# luchador.net
KiCad netlist of a schematic drawn in EAGLE
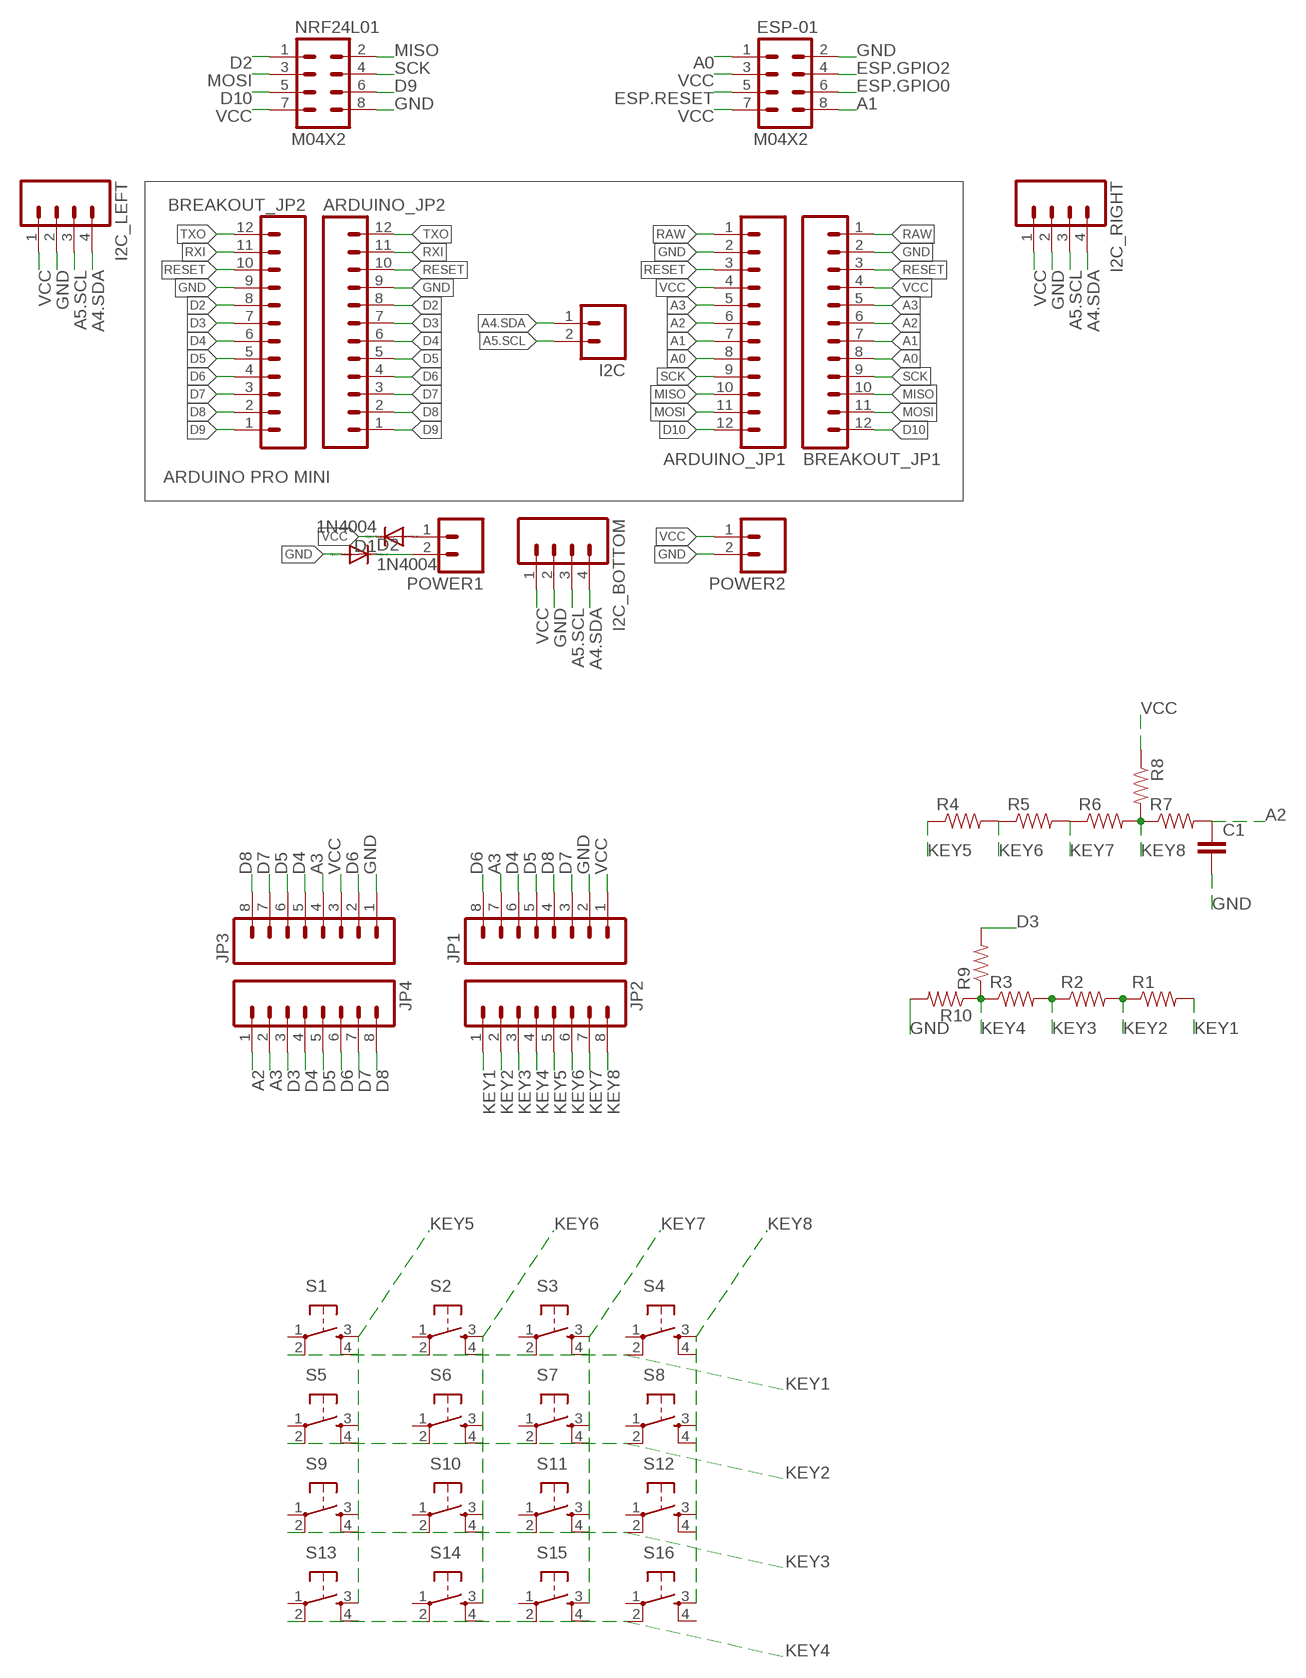
[diagram p0: schematic, sheet 1]

(export (version "E")
  (design (tool "Eeschema 10.0.6"))
  (components
    (comp (ref "ARDUINO_JP1")
      (value "M12PTH")
      (footprint "eagle-import:1X12")
      (libsource (lib "eagle-import") (part "M12PTH"))
    )
    (comp (ref "ARDUINO_JP2")
      (value "M12PTH")
      (footprint "eagle-import:1X12")
      (libsource (lib "eagle-import") (part "M12PTH"))
    )
    (comp (ref "BREAKOUT_JP1")
      (value "M12PTH")
      (footprint "eagle-import:1X12")
      (libsource (lib "eagle-import") (part "M12PTH"))
    )
    (comp (ref "BREAKOUT_JP2")
      (value "M12PTH")
      (footprint "eagle-import:1X12")
      (libsource (lib "eagle-import") (part "M12PTH"))
    )
    (comp (ref "C1")
      (value "CAP_")
      (footprint "eagle-import:AXIAL-5MM")
      (libsource (lib "eagle-import") (part "CAP_"))
    )
    (comp (ref "D1")
      (value "1N4004")
      (footprint "eagle-import:DO41-10")
      (libsource (lib "eagle-import") (part "1N4004"))
    )
    (comp (ref "D2")
      (value "1N4004")
      (footprint "eagle-import:DO41-10")
      (libsource (lib "eagle-import") (part "1N4004"))
    )
    (comp (ref "ESP-01")
      (value "M04X2")
      (footprint "eagle-import:2X4")
      (libsource (lib "eagle-import") (part "M04X2"))
    )
    (comp (ref "I2C")
      (value "M02PTH")
      (footprint "eagle-import:1X02")
      (libsource (lib "eagle-import") (part "M02PTH"))
    )
    (comp (ref "I2C_BOTTOM")
      (value "M04PTH")
      (footprint "eagle-import:1X04")
      (libsource (lib "eagle-import") (part "M04PTH"))
    )
    (comp (ref "I2C_LEFT")
      (value "M04PTH")
      (footprint "eagle-import:1X04")
      (libsource (lib "eagle-import") (part "M04PTH"))
    )
    (comp (ref "I2C_RIGHT")
      (value "M04PTH")
      (footprint "eagle-import:1X04")
      (libsource (lib "eagle-import") (part "M04PTH"))
    )
    (comp (ref "JP1")
      (value "M08SILK_FEMALE_PTH")
      (footprint "eagle-import:1X08")
      (libsource (lib "eagle-import") (part "M08SILK_FEMALE_PTH"))
    )
    (comp (ref "JP2")
      (value "M08SILK_FEMALE_PTH")
      (footprint "eagle-import:1X08")
      (libsource (lib "eagle-import") (part "M08SILK_FEMALE_PTH"))
    )
    (comp (ref "JP3")
      (value "M08SILK_FEMALE_PTH")
      (footprint "eagle-import:1X08")
      (libsource (lib "eagle-import") (part "M08SILK_FEMALE_PTH"))
    )
    (comp (ref "JP4")
      (value "M08SILK_FEMALE_PTH")
      (footprint "eagle-import:1X08")
      (libsource (lib "eagle-import") (part "M08SILK_FEMALE_PTH"))
    )
    (comp (ref "NRF24L01")
      (value "M04X2")
      (footprint "eagle-import:2X4")
      (libsource (lib "eagle-import") (part "M04X2"))
    )
    (comp (ref "POWER1")
      (value "M02PTH")
      (footprint "eagle-import:1X02")
      (libsource (lib "eagle-import") (part "M02PTH"))
    )
    (comp (ref "POWER2")
      (value "M02PTH")
      (footprint "eagle-import:1X02")
      (libsource (lib "eagle-import") (part "M02PTH"))
    )
    (comp (ref "R1")
      (value "RESISTORAXIAL-0.3")
      (footprint "eagle-import:AXIAL-0.3")
      (libsource (lib "eagle-import") (part "RESISTORAXIAL-0.3"))
    )
    (comp (ref "R2")
      (value "RESISTORAXIAL-0.3")
      (footprint "eagle-import:AXIAL-0.3")
      (libsource (lib "eagle-import") (part "RESISTORAXIAL-0.3"))
    )
    (comp (ref "R3")
      (value "RESISTORAXIAL-0.3")
      (footprint "eagle-import:AXIAL-0.3")
      (libsource (lib "eagle-import") (part "RESISTORAXIAL-0.3"))
    )
    (comp (ref "R4")
      (value "RESISTORAXIAL-0.3")
      (footprint "eagle-import:AXIAL-0.3")
      (libsource (lib "eagle-import") (part "RESISTORAXIAL-0.3"))
    )
    (comp (ref "R5")
      (value "RESISTORAXIAL-0.3")
      (footprint "eagle-import:AXIAL-0.3")
      (libsource (lib "eagle-import") (part "RESISTORAXIAL-0.3"))
    )
    (comp (ref "R6")
      (value "RESISTORAXIAL-0.3")
      (footprint "eagle-import:AXIAL-0.3")
      (libsource (lib "eagle-import") (part "RESISTORAXIAL-0.3"))
    )
    (comp (ref "R7")
      (value "RESISTORAXIAL-0.3")
      (footprint "eagle-import:AXIAL-0.3")
      (libsource (lib "eagle-import") (part "RESISTORAXIAL-0.3"))
    )
    (comp (ref "R8")
      (value "RESISTORAXIAL-0.3")
      (footprint "eagle-import:AXIAL-0.3")
      (libsource (lib "eagle-import") (part "RESISTORAXIAL-0.3"))
    )
    (comp (ref "R9")
      (value "RESISTORAXIAL-0.3")
      (footprint "eagle-import:AXIAL-0.3")
      (libsource (lib "eagle-import") (part "RESISTORAXIAL-0.3"))
    )
    (comp (ref "R10")
      (value "RESISTORAXIAL-0.3")
      (footprint "eagle-import:AXIAL-0.3")
      (libsource (lib "eagle-import") (part "RESISTORAXIAL-0.3"))
    )
    (comp (ref "S1")
      (value "TAC_SWITCHPTH")
      (footprint "eagle-import:TACTILE-PTH")
      (libsource (lib "eagle-import") (part "TAC_SWITCHPTH"))
    )
    (comp (ref "S2")
      (value "TAC_SWITCHPTH")
      (footprint "eagle-import:TACTILE-PTH")
      (libsource (lib "eagle-import") (part "TAC_SWITCHPTH"))
    )
    (comp (ref "S3")
      (value "TAC_SWITCHPTH")
      (footprint "eagle-import:TACTILE-PTH")
      (libsource (lib "eagle-import") (part "TAC_SWITCHPTH"))
    )
    (comp (ref "S4")
      (value "TAC_SWITCHPTH")
      (footprint "eagle-import:TACTILE-PTH")
      (libsource (lib "eagle-import") (part "TAC_SWITCHPTH"))
    )
    (comp (ref "S5")
      (value "TAC_SWITCHPTH")
      (footprint "eagle-import:TACTILE-PTH")
      (libsource (lib "eagle-import") (part "TAC_SWITCHPTH"))
    )
    (comp (ref "S6")
      (value "TAC_SWITCHPTH")
      (footprint "eagle-import:TACTILE-PTH")
      (libsource (lib "eagle-import") (part "TAC_SWITCHPTH"))
    )
    (comp (ref "S7")
      (value "TAC_SWITCHPTH")
      (footprint "eagle-import:TACTILE-PTH")
      (libsource (lib "eagle-import") (part "TAC_SWITCHPTH"))
    )
    (comp (ref "S8")
      (value "TAC_SWITCHPTH")
      (footprint "eagle-import:TACTILE-PTH")
      (libsource (lib "eagle-import") (part "TAC_SWITCHPTH"))
    )
    (comp (ref "S9")
      (value "TAC_SWITCHPTH")
      (footprint "eagle-import:TACTILE-PTH")
      (libsource (lib "eagle-import") (part "TAC_SWITCHPTH"))
    )
    (comp (ref "S10")
      (value "TAC_SWITCHPTH")
      (footprint "eagle-import:TACTILE-PTH")
      (libsource (lib "eagle-import") (part "TAC_SWITCHPTH"))
    )
    (comp (ref "S11")
      (value "TAC_SWITCHPTH")
      (footprint "eagle-import:TACTILE-PTH")
      (libsource (lib "eagle-import") (part "TAC_SWITCHPTH"))
    )
    (comp (ref "S12")
      (value "TAC_SWITCHPTH")
      (footprint "eagle-import:TACTILE-PTH")
      (libsource (lib "eagle-import") (part "TAC_SWITCHPTH"))
    )
    (comp (ref "S13")
      (value "TAC_SWITCHPTH")
      (footprint "eagle-import:TACTILE-PTH")
      (libsource (lib "eagle-import") (part "TAC_SWITCHPTH"))
    )
    (comp (ref "S14")
      (value "TAC_SWITCHPTH")
      (footprint "eagle-import:TACTILE-PTH")
      (libsource (lib "eagle-import") (part "TAC_SWITCHPTH"))
    )
    (comp (ref "S15")
      (value "TAC_SWITCHPTH")
      (footprint "eagle-import:TACTILE-PTH")
      (libsource (lib "eagle-import") (part "TAC_SWITCHPTH"))
    )
    (comp (ref "S16")
      (value "TAC_SWITCHPTH")
      (footprint "eagle-import:TACTILE-PTH")
      (libsource (lib "eagle-import") (part "TAC_SWITCHPTH"))
    )
  )
  (nets
    (net (code "1") (name "/ESP.GPIO0") (class "Default")
      (node (ref "ESP-01") (pin "6") (pinfunction "6_6") (pintype "passive"))
    )
    (net (code "2") (name "/ESP.GPIO2") (class "Default")
      (node (ref "ESP-01") (pin "4") (pinfunction "4_4") (pintype "passive"))
    )
    (net (code "3") (name "/ESP.RESET") (class "Default")
      (node (ref "ESP-01") (pin "5") (pinfunction "5_5") (pintype "passive"))
    )
    (net (code "4") (name "/KEY1") (class "Default")
      (node (ref "JP2") (pin "1") (pinfunction "1_1") (pintype "passive"))
      (node (ref "R1") (pin "P$2") (pinfunction "2_P$2") (pintype "passive"))
      (node (ref "S1") (pin "2") (pinfunction "2_2") (pintype "passive"))
      (node (ref "S2") (pin "2") (pinfunction "2_2") (pintype "passive"))
      (node (ref "S3") (pin "2") (pinfunction "2_2") (pintype "passive"))
      (node (ref "S4") (pin "2") (pinfunction "2_2") (pintype "passive"))
    )
    (net (code "5") (name "/KEY2") (class "Default")
      (node (ref "JP2") (pin "2") (pinfunction "2_2") (pintype "passive"))
      (node (ref "R1") (pin "P$1") (pinfunction "1_P$1") (pintype "passive"))
      (node (ref "R2") (pin "P$2") (pinfunction "2_P$2") (pintype "passive"))
      (node (ref "S5") (pin "2") (pinfunction "2_2") (pintype "passive"))
      (node (ref "S6") (pin "2") (pinfunction "2_2") (pintype "passive"))
      (node (ref "S7") (pin "2") (pinfunction "2_2") (pintype "passive"))
      (node (ref "S8") (pin "2") (pinfunction "2_2") (pintype "passive"))
    )
    (net (code "6") (name "/KEY3") (class "Default")
      (node (ref "JP2") (pin "3") (pinfunction "3_3") (pintype "passive"))
      (node (ref "R2") (pin "P$1") (pinfunction "1_P$1") (pintype "passive"))
      (node (ref "R3") (pin "P$2") (pinfunction "2_P$2") (pintype "passive"))
      (node (ref "S10") (pin "2") (pinfunction "2_2") (pintype "passive"))
      (node (ref "S11") (pin "2") (pinfunction "2_2") (pintype "passive"))
      (node (ref "S12") (pin "2") (pinfunction "2_2") (pintype "passive"))
      (node (ref "S9") (pin "2") (pinfunction "2_2") (pintype "passive"))
    )
    (net (code "7") (name "/KEY4") (class "Default")
      (node (ref "JP2") (pin "4") (pinfunction "4_4") (pintype "passive"))
      (node (ref "R10") (pin "P$1") (pinfunction "1_P$1") (pintype "passive"))
      (node (ref "R3") (pin "P$1") (pinfunction "1_P$1") (pintype "passive"))
      (node (ref "R9") (pin "P$1") (pinfunction "1_P$1") (pintype "passive"))
      (node (ref "S13") (pin "2") (pinfunction "2_2") (pintype "passive"))
      (node (ref "S14") (pin "2") (pinfunction "2_2") (pintype "passive"))
      (node (ref "S15") (pin "2") (pinfunction "2_2") (pintype "passive"))
      (node (ref "S16") (pin "2") (pinfunction "2_2") (pintype "passive"))
    )
    (net (code "8") (name "/KEY5") (class "Default")
      (node (ref "JP2") (pin "5") (pinfunction "5_5") (pintype "passive"))
      (node (ref "R4") (pin "P$1") (pinfunction "1_P$1") (pintype "passive"))
      (node (ref "S1") (pin "3") (pinfunction "3_3") (pintype "passive"))
      (node (ref "S13") (pin "3") (pinfunction "3_3") (pintype "passive"))
      (node (ref "S5") (pin "3") (pinfunction "3_3") (pintype "passive"))
      (node (ref "S9") (pin "3") (pinfunction "3_3") (pintype "passive"))
    )
    (net (code "9") (name "/KEY6") (class "Default")
      (node (ref "JP2") (pin "6") (pinfunction "6_6") (pintype "passive"))
      (node (ref "R4") (pin "P$2") (pinfunction "2_P$2") (pintype "passive"))
      (node (ref "R5") (pin "P$1") (pinfunction "1_P$1") (pintype "passive"))
      (node (ref "S10") (pin "3") (pinfunction "3_3") (pintype "passive"))
      (node (ref "S14") (pin "3") (pinfunction "3_3") (pintype "passive"))
      (node (ref "S2") (pin "3") (pinfunction "3_3") (pintype "passive"))
      (node (ref "S6") (pin "3") (pinfunction "3_3") (pintype "passive"))
    )
    (net (code "10") (name "/KEY7") (class "Default")
      (node (ref "JP2") (pin "7") (pinfunction "7_7") (pintype "passive"))
      (node (ref "R5") (pin "P$2") (pinfunction "2_P$2") (pintype "passive"))
      (node (ref "R6") (pin "P$1") (pinfunction "1_P$1") (pintype "passive"))
      (node (ref "S11") (pin "3") (pinfunction "3_3") (pintype "passive"))
      (node (ref "S15") (pin "3") (pinfunction "3_3") (pintype "passive"))
      (node (ref "S3") (pin "3") (pinfunction "3_3") (pintype "passive"))
      (node (ref "S7") (pin "3") (pinfunction "3_3") (pintype "passive"))
    )
    (net (code "11") (name "/KEY8") (class "Default")
      (node (ref "JP2") (pin "8") (pinfunction "8_8") (pintype "passive"))
      (node (ref "R6") (pin "P$2") (pinfunction "2_P$2") (pintype "passive"))
      (node (ref "R7") (pin "P$1") (pinfunction "1_P$1") (pintype "passive"))
      (node (ref "R8") (pin "P$2") (pinfunction "2_P$2") (pintype "passive"))
      (node (ref "S12") (pin "3") (pinfunction "3_3") (pintype "passive"))
      (node (ref "S16") (pin "3") (pinfunction "3_3") (pintype "passive"))
      (node (ref "S4") (pin "3") (pinfunction "3_3") (pintype "passive"))
      (node (ref "S8") (pin "3") (pinfunction "3_3") (pintype "passive"))
    )
    (net (code "12") (name "A0") (class "Default")
      (node (ref "ARDUINO_JP1") (pin "8") (pinfunction "8_8") (pintype "passive"))
      (node (ref "BREAKOUT_JP1") (pin "8") (pinfunction "8_8") (pintype "passive"))
      (node (ref "ESP-01") (pin "1") (pinfunction "1_1") (pintype "passive"))
    )
    (net (code "13") (name "A1") (class "Default")
      (node (ref "ARDUINO_JP1") (pin "7") (pinfunction "7_7") (pintype "passive"))
      (node (ref "BREAKOUT_JP1") (pin "7") (pinfunction "7_7") (pintype "passive"))
      (node (ref "ESP-01") (pin "8") (pinfunction "8_8") (pintype "passive"))
    )
    (net (code "14") (name "A2") (class "Default")
      (node (ref "ARDUINO_JP1") (pin "6") (pinfunction "6_6") (pintype "passive"))
      (node (ref "BREAKOUT_JP1") (pin "6") (pinfunction "6_6") (pintype "passive"))
      (node (ref "C1") (pin "P$1") (pinfunction "1_P$1") (pintype "passive"))
      (node (ref "JP4") (pin "1") (pinfunction "1_1") (pintype "passive"))
      (node (ref "R7") (pin "P$2") (pinfunction "2_P$2") (pintype "passive"))
    )
    (net (code "15") (name "A3") (class "Default")
      (node (ref "ARDUINO_JP1") (pin "5") (pinfunction "5_5") (pintype "passive"))
      (node (ref "BREAKOUT_JP1") (pin "5") (pinfunction "5_5") (pintype "passive"))
      (node (ref "JP1") (pin "7") (pinfunction "7_7") (pintype "passive"))
      (node (ref "JP3") (pin "4") (pinfunction "4_4") (pintype "passive"))
      (node (ref "JP4") (pin "2") (pinfunction "2_2") (pintype "passive"))
    )
    (net (code "16") (name "A4.SDA") (class "Default")
      (node (ref "I2C") (pin "1") (pinfunction "1_1") (pintype "passive"))
      (node (ref "I2C_BOTTOM") (pin "4") (pinfunction "4_4") (pintype "passive"))
      (node (ref "I2C_LEFT") (pin "4") (pinfunction "4_4") (pintype "passive"))
      (node (ref "I2C_RIGHT") (pin "4") (pinfunction "4_4") (pintype "passive"))
    )
    (net (code "17") (name "A5.SCL") (class "Default")
      (node (ref "I2C") (pin "2") (pinfunction "2_2") (pintype "passive"))
      (node (ref "I2C_BOTTOM") (pin "3") (pinfunction "3_3") (pintype "passive"))
      (node (ref "I2C_LEFT") (pin "3") (pinfunction "3_3") (pintype "passive"))
      (node (ref "I2C_RIGHT") (pin "3") (pinfunction "3_3") (pintype "passive"))
    )
    (net (code "18") (name "D2") (class "Default")
      (node (ref "ARDUINO_JP2") (pin "8") (pinfunction "8_8") (pintype "passive"))
      (node (ref "BREAKOUT_JP2") (pin "8") (pinfunction "8_8") (pintype "passive"))
      (node (ref "NRF24L01") (pin "1") (pinfunction "1_1") (pintype "passive"))
    )
    (net (code "19") (name "D3") (class "Default")
      (node (ref "ARDUINO_JP2") (pin "7") (pinfunction "7_7") (pintype "passive"))
      (node (ref "BREAKOUT_JP2") (pin "7") (pinfunction "7_7") (pintype "passive"))
      (node (ref "JP4") (pin "3") (pinfunction "3_3") (pintype "passive"))
      (node (ref "R9") (pin "P$2") (pinfunction "2_P$2") (pintype "passive"))
    )
    (net (code "20") (name "D4") (class "Default")
      (node (ref "ARDUINO_JP2") (pin "6") (pinfunction "6_6") (pintype "passive"))
      (node (ref "BREAKOUT_JP2") (pin "6") (pinfunction "6_6") (pintype "passive"))
      (node (ref "JP1") (pin "6") (pinfunction "6_6") (pintype "passive"))
      (node (ref "JP3") (pin "5") (pinfunction "5_5") (pintype "passive"))
      (node (ref "JP4") (pin "4") (pinfunction "4_4") (pintype "passive"))
    )
    (net (code "21") (name "D5") (class "Default")
      (node (ref "ARDUINO_JP2") (pin "5") (pinfunction "5_5") (pintype "passive"))
      (node (ref "BREAKOUT_JP2") (pin "5") (pinfunction "5_5") (pintype "passive"))
      (node (ref "JP1") (pin "5") (pinfunction "5_5") (pintype "passive"))
      (node (ref "JP3") (pin "6") (pinfunction "6_6") (pintype "passive"))
      (node (ref "JP4") (pin "5") (pinfunction "5_5") (pintype "passive"))
    )
    (net (code "22") (name "D6") (class "Default")
      (node (ref "ARDUINO_JP2") (pin "4") (pinfunction "4_4") (pintype "passive"))
      (node (ref "BREAKOUT_JP2") (pin "4") (pinfunction "4_4") (pintype "passive"))
      (node (ref "JP1") (pin "8") (pinfunction "8_8") (pintype "passive"))
      (node (ref "JP3") (pin "2") (pinfunction "2_2") (pintype "passive"))
      (node (ref "JP4") (pin "6") (pinfunction "6_6") (pintype "passive"))
    )
    (net (code "23") (name "D7") (class "Default")
      (node (ref "ARDUINO_JP2") (pin "3") (pinfunction "3_3") (pintype "passive"))
      (node (ref "BREAKOUT_JP2") (pin "3") (pinfunction "3_3") (pintype "passive"))
      (node (ref "JP1") (pin "3") (pinfunction "3_3") (pintype "passive"))
      (node (ref "JP3") (pin "7") (pinfunction "7_7") (pintype "passive"))
      (node (ref "JP4") (pin "7") (pinfunction "7_7") (pintype "passive"))
    )
    (net (code "24") (name "D8") (class "Default")
      (node (ref "ARDUINO_JP2") (pin "2") (pinfunction "2_2") (pintype "passive"))
      (node (ref "BREAKOUT_JP2") (pin "2") (pinfunction "2_2") (pintype "passive"))
      (node (ref "JP1") (pin "4") (pinfunction "4_4") (pintype "passive"))
      (node (ref "JP3") (pin "8") (pinfunction "8_8") (pintype "passive"))
      (node (ref "JP4") (pin "8") (pinfunction "8_8") (pintype "passive"))
    )
    (net (code "25") (name "D9") (class "Default")
      (node (ref "ARDUINO_JP2") (pin "1") (pinfunction "1_1") (pintype "passive"))
      (node (ref "BREAKOUT_JP2") (pin "1") (pinfunction "1_1") (pintype "passive"))
      (node (ref "NRF24L01") (pin "6") (pinfunction "6_6") (pintype "passive"))
    )
    (net (code "26") (name "D10") (class "Default")
      (node (ref "ARDUINO_JP1") (pin "12") (pinfunction "12_12") (pintype "passive"))
      (node (ref "BREAKOUT_JP1") (pin "12") (pinfunction "12_12") (pintype "passive"))
      (node (ref "NRF24L01") (pin "5") (pinfunction "5_5") (pintype "passive"))
    )
    (net (code "27") (name "GND") (class "Default")
      (node (ref "ARDUINO_JP1") (pin "2") (pinfunction "2_2") (pintype "passive"))
      (node (ref "ARDUINO_JP2") (pin "9") (pinfunction "9_9") (pintype "passive"))
      (node (ref "BREAKOUT_JP1") (pin "2") (pinfunction "2_2") (pintype "passive"))
      (node (ref "BREAKOUT_JP2") (pin "9") (pinfunction "9_9") (pintype "passive"))
      (node (ref "C1") (pin "P$2") (pinfunction "2_P$2") (pintype "passive"))
      (node (ref "D2") (pin "A") (pinfunction "A_A") (pintype "passive"))
      (node (ref "ESP-01") (pin "2") (pinfunction "2_2") (pintype "passive"))
      (node (ref "I2C_BOTTOM") (pin "2") (pinfunction "2_2") (pintype "passive"))
      (node (ref "I2C_LEFT") (pin "2") (pinfunction "2_2") (pintype "passive"))
      (node (ref "I2C_RIGHT") (pin "2") (pinfunction "2_2") (pintype "passive"))
      (node (ref "JP1") (pin "2") (pinfunction "2_2") (pintype "passive"))
      (node (ref "JP3") (pin "1") (pinfunction "1_1") (pintype "passive"))
      (node (ref "NRF24L01") (pin "8") (pinfunction "8_8") (pintype "passive"))
      (node (ref "POWER2") (pin "2") (pinfunction "2_2") (pintype "passive"))
      (node (ref "R10") (pin "P$2") (pinfunction "2_P$2") (pintype "passive"))
    )
    (net (code "28") (name "MISO") (class "Default")
      (node (ref "ARDUINO_JP1") (pin "10") (pinfunction "10_10") (pintype "passive"))
      (node (ref "BREAKOUT_JP1") (pin "10") (pinfunction "10_10") (pintype "passive"))
      (node (ref "NRF24L01") (pin "2") (pinfunction "2_2") (pintype "passive"))
    )
    (net (code "29") (name "MOSI") (class "Default")
      (node (ref "ARDUINO_JP1") (pin "11") (pinfunction "11_11") (pintype "passive"))
      (node (ref "BREAKOUT_JP1") (pin "11") (pinfunction "11_11") (pintype "passive"))
      (node (ref "NRF24L01") (pin "3") (pinfunction "3_3") (pintype "passive"))
    )
    (net (code "30") (name "Net-(D1-PadA)") (class "Default")
      (node (ref "D1") (pin "A") (pinfunction "A_A") (pintype "passive"))
      (node (ref "POWER1") (pin "1") (pinfunction "1_1") (pintype "passive"))
    )
    (net (code "31") (name "Net-(D2-PadC)") (class "Default")
      (node (ref "D2") (pin "C") (pinfunction "C_C") (pintype "passive"))
      (node (ref "POWER1") (pin "2") (pinfunction "2_2") (pintype "passive"))
    )
    (net (code "32") (name "RAW") (class "Default")
      (node (ref "ARDUINO_JP1") (pin "1") (pinfunction "1_1") (pintype "passive"))
      (node (ref "BREAKOUT_JP1") (pin "1") (pinfunction "1_1") (pintype "passive"))
    )
    (net (code "33") (name "RESET") (class "Default")
      (node (ref "ARDUINO_JP1") (pin "3") (pinfunction "3_3") (pintype "passive"))
      (node (ref "ARDUINO_JP2") (pin "10") (pinfunction "10_10") (pintype "passive"))
      (node (ref "BREAKOUT_JP1") (pin "3") (pinfunction "3_3") (pintype "passive"))
      (node (ref "BREAKOUT_JP2") (pin "10") (pinfunction "10_10") (pintype "passive"))
    )
    (net (code "34") (name "RXI") (class "Default")
      (node (ref "ARDUINO_JP2") (pin "11") (pinfunction "11_11") (pintype "passive"))
      (node (ref "BREAKOUT_JP2") (pin "11") (pinfunction "11_11") (pintype "passive"))
    )
    (net (code "35") (name "SCK") (class "Default")
      (node (ref "ARDUINO_JP1") (pin "9") (pinfunction "9_9") (pintype "passive"))
      (node (ref "BREAKOUT_JP1") (pin "9") (pinfunction "9_9") (pintype "passive"))
      (node (ref "NRF24L01") (pin "4") (pinfunction "4_4") (pintype "passive"))
    )
    (net (code "36") (name "TXO") (class "Default")
      (node (ref "ARDUINO_JP2") (pin "12") (pinfunction "12_12") (pintype "passive"))
      (node (ref "BREAKOUT_JP2") (pin "12") (pinfunction "12_12") (pintype "passive"))
    )
    (net (code "37") (name "VCC") (class "Default")
      (node (ref "ARDUINO_JP1") (pin "4") (pinfunction "4_4") (pintype "passive"))
      (node (ref "BREAKOUT_JP1") (pin "4") (pinfunction "4_4") (pintype "passive"))
      (node (ref "D1") (pin "C") (pinfunction "C_C") (pintype "passive"))
      (node (ref "ESP-01") (pin "3") (pinfunction "3_3") (pintype "passive"))
      (node (ref "ESP-01") (pin "7") (pinfunction "7_7") (pintype "passive"))
      (node (ref "I2C_BOTTOM") (pin "1") (pinfunction "1_1") (pintype "passive"))
      (node (ref "I2C_LEFT") (pin "1") (pinfunction "1_1") (pintype "passive"))
      (node (ref "I2C_RIGHT") (pin "1") (pinfunction "1_1") (pintype "passive"))
      (node (ref "JP1") (pin "1") (pinfunction "1_1") (pintype "passive"))
      (node (ref "JP3") (pin "3") (pinfunction "3_3") (pintype "passive"))
      (node (ref "NRF24L01") (pin "7") (pinfunction "7_7") (pintype "passive"))
      (node (ref "POWER2") (pin "1") (pinfunction "1_1") (pintype "passive"))
      (node (ref "R8") (pin "P$1") (pinfunction "1_P$1") (pintype "passive"))
    )
    (net (code "38") (name "unconnected-(S1-Pad1)") (class "Default")
      (node (ref "S1") (pin "1") (pinfunction "1_1") (pintype "passive"))
    )
    (net (code "39") (name "unconnected-(S1-Pad4)") (class "Default")
      (node (ref "S1") (pin "4") (pinfunction "4_4") (pintype "passive"))
    )
    (net (code "40") (name "unconnected-(S2-Pad1)") (class "Default")
      (node (ref "S2") (pin "1") (pinfunction "1_1") (pintype "passive"))
    )
    (net (code "41") (name "unconnected-(S2-Pad4)") (class "Default")
      (node (ref "S2") (pin "4") (pinfunction "4_4") (pintype "passive"))
    )
    (net (code "42") (name "unconnected-(S3-Pad1)") (class "Default")
      (node (ref "S3") (pin "1") (pinfunction "1_1") (pintype "passive"))
    )
    (net (code "43") (name "unconnected-(S3-Pad4)") (class "Default")
      (node (ref "S3") (pin "4") (pinfunction "4_4") (pintype "passive"))
    )
    (net (code "44") (name "unconnected-(S4-Pad1)") (class "Default")
      (node (ref "S4") (pin "1") (pinfunction "1_1") (pintype "passive"))
    )
    (net (code "45") (name "unconnected-(S4-Pad4)") (class "Default")
      (node (ref "S4") (pin "4") (pinfunction "4_4") (pintype "passive"))
    )
    (net (code "46") (name "unconnected-(S5-Pad1)") (class "Default")
      (node (ref "S5") (pin "1") (pinfunction "1_1") (pintype "passive"))
    )
    (net (code "47") (name "unconnected-(S5-Pad4)") (class "Default")
      (node (ref "S5") (pin "4") (pinfunction "4_4") (pintype "passive"))
    )
    (net (code "48") (name "unconnected-(S6-Pad1)") (class "Default")
      (node (ref "S6") (pin "1") (pinfunction "1_1") (pintype "passive"))
    )
    (net (code "49") (name "unconnected-(S6-Pad4)") (class "Default")
      (node (ref "S6") (pin "4") (pinfunction "4_4") (pintype "passive"))
    )
    (net (code "50") (name "unconnected-(S7-Pad1)") (class "Default")
      (node (ref "S7") (pin "1") (pinfunction "1_1") (pintype "passive"))
    )
    (net (code "51") (name "unconnected-(S7-Pad4)") (class "Default")
      (node (ref "S7") (pin "4") (pinfunction "4_4") (pintype "passive"))
    )
    (net (code "52") (name "unconnected-(S8-Pad1)") (class "Default")
      (node (ref "S8") (pin "1") (pinfunction "1_1") (pintype "passive"))
    )
    (net (code "53") (name "unconnected-(S8-Pad4)") (class "Default")
      (node (ref "S8") (pin "4") (pinfunction "4_4") (pintype "passive"))
    )
    (net (code "54") (name "unconnected-(S9-Pad1)") (class "Default")
      (node (ref "S9") (pin "1") (pinfunction "1_1") (pintype "passive"))
    )
    (net (code "55") (name "unconnected-(S9-Pad4)") (class "Default")
      (node (ref "S9") (pin "4") (pinfunction "4_4") (pintype "passive"))
    )
    (net (code "56") (name "unconnected-(S10-Pad1)") (class "Default")
      (node (ref "S10") (pin "1") (pinfunction "1_1") (pintype "passive"))
    )
    (net (code "57") (name "unconnected-(S10-Pad4)") (class "Default")
      (node (ref "S10") (pin "4") (pinfunction "4_4") (pintype "passive"))
    )
    (net (code "58") (name "unconnected-(S11-Pad1)") (class "Default")
      (node (ref "S11") (pin "1") (pinfunction "1_1") (pintype "passive"))
    )
    (net (code "59") (name "unconnected-(S11-Pad4)") (class "Default")
      (node (ref "S11") (pin "4") (pinfunction "4_4") (pintype "passive"))
    )
    (net (code "60") (name "unconnected-(S12-Pad1)") (class "Default")
      (node (ref "S12") (pin "1") (pinfunction "1_1") (pintype "passive"))
    )
    (net (code "61") (name "unconnected-(S12-Pad4)") (class "Default")
      (node (ref "S12") (pin "4") (pinfunction "4_4") (pintype "passive"))
    )
    (net (code "62") (name "unconnected-(S13-Pad1)") (class "Default")
      (node (ref "S13") (pin "1") (pinfunction "1_1") (pintype "passive"))
    )
    (net (code "63") (name "unconnected-(S13-Pad4)") (class "Default")
      (node (ref "S13") (pin "4") (pinfunction "4_4") (pintype "passive"))
    )
    (net (code "64") (name "unconnected-(S14-Pad1)") (class "Default")
      (node (ref "S14") (pin "1") (pinfunction "1_1") (pintype "passive"))
    )
    (net (code "65") (name "unconnected-(S14-Pad4)") (class "Default")
      (node (ref "S14") (pin "4") (pinfunction "4_4") (pintype "passive"))
    )
    (net (code "66") (name "unconnected-(S15-Pad1)") (class "Default")
      (node (ref "S15") (pin "1") (pinfunction "1_1") (pintype "passive"))
    )
    (net (code "67") (name "unconnected-(S15-Pad4)") (class "Default")
      (node (ref "S15") (pin "4") (pinfunction "4_4") (pintype "passive"))
    )
    (net (code "68") (name "unconnected-(S16-Pad1)") (class "Default")
      (node (ref "S16") (pin "1") (pinfunction "1_1") (pintype "passive"))
    )
    (net (code "69") (name "unconnected-(S16-Pad4)") (class "Default")
      (node (ref "S16") (pin "4") (pinfunction "4_4") (pintype "passive"))
    )
  )
)
